# SENSE.net
KiCad netlist of a schematic drawn in Altium Designer
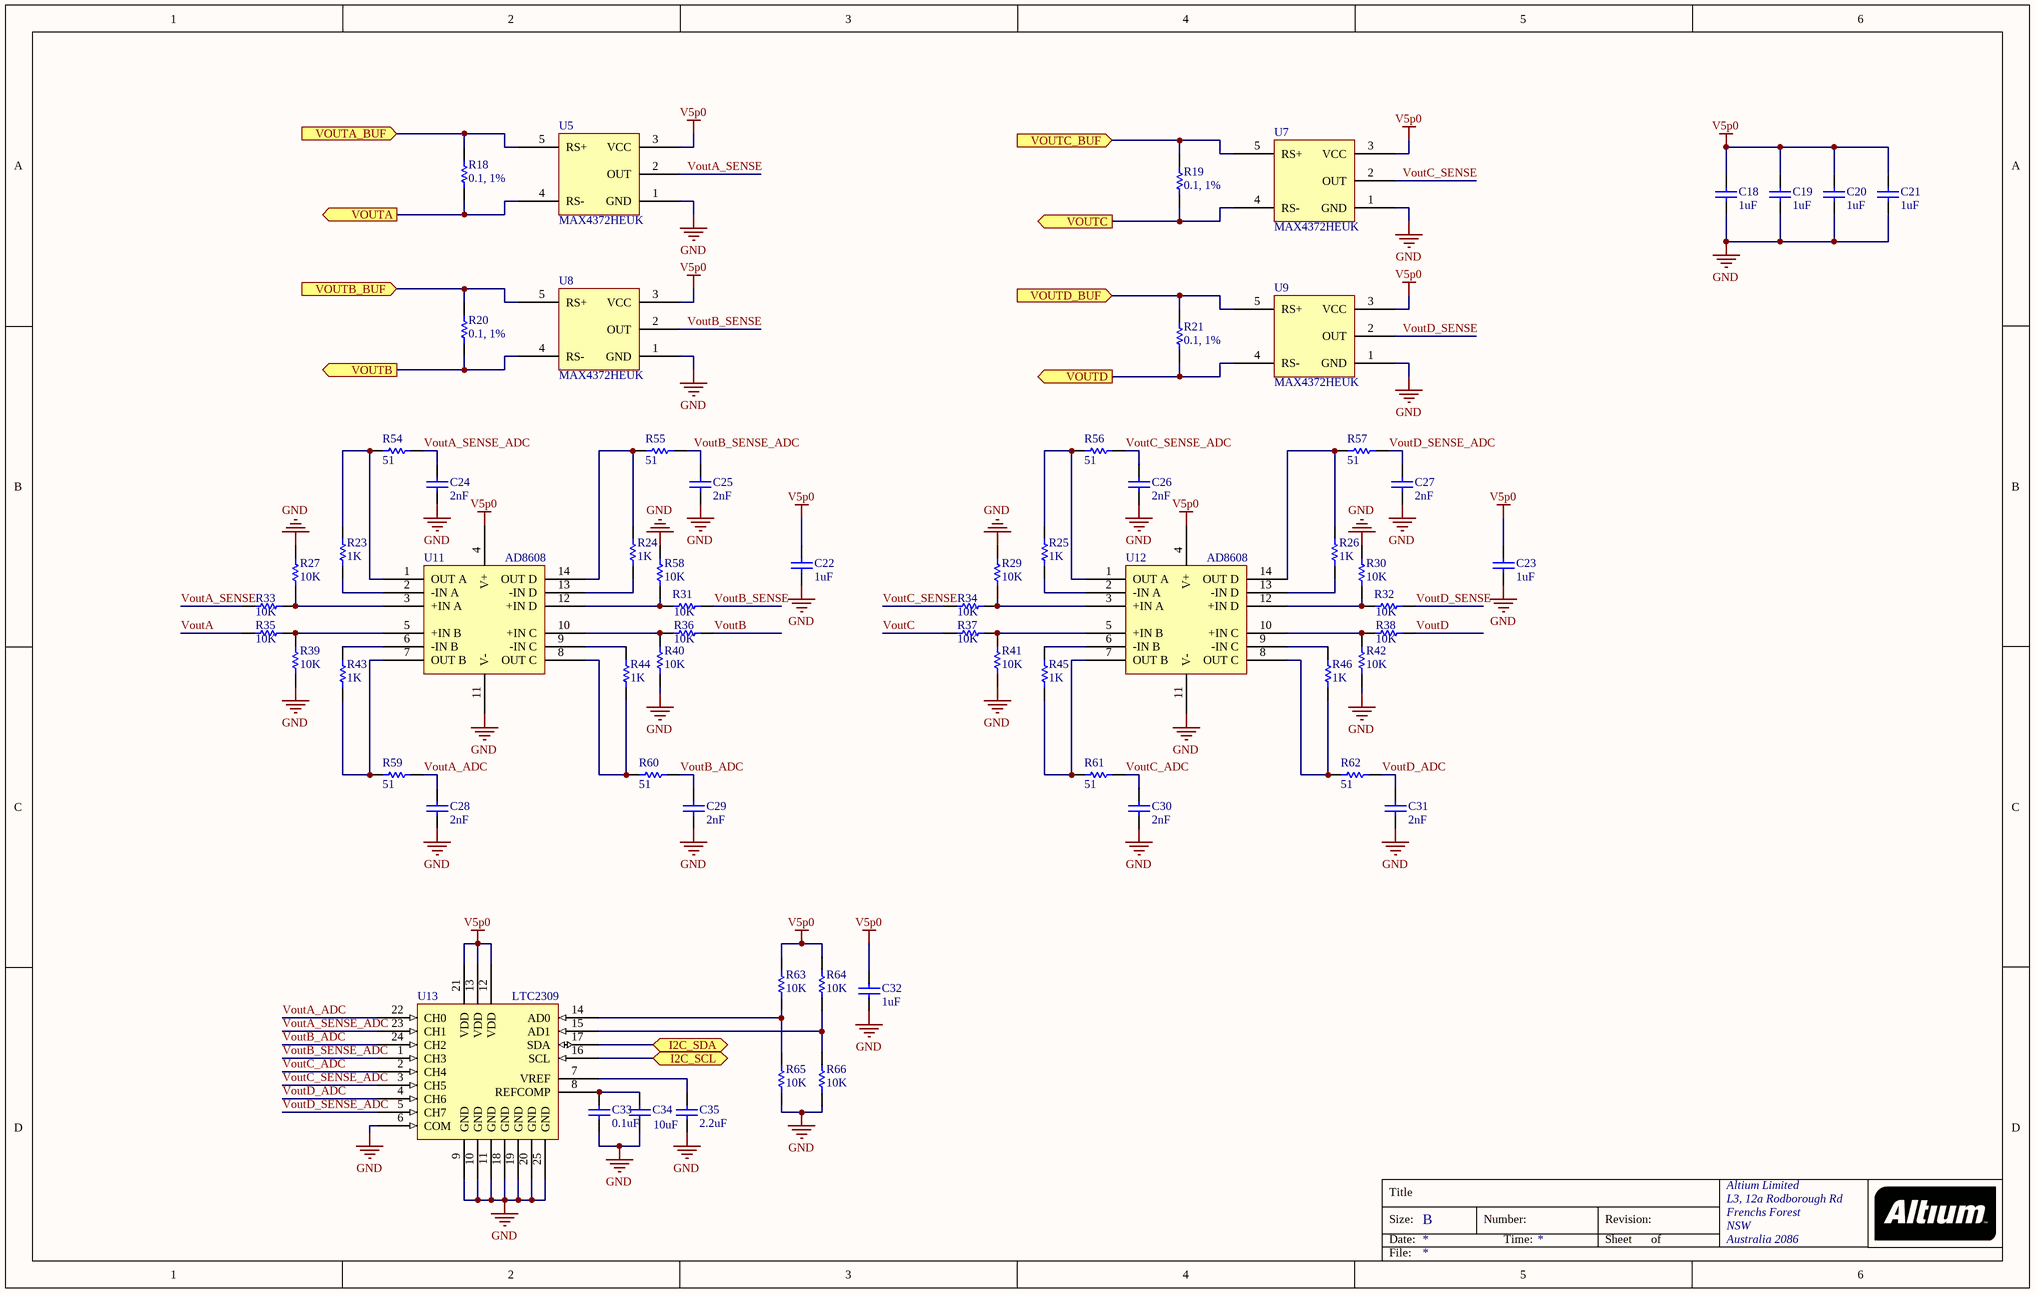
[diagram p0: SENSE.SchDoc]

(export (version "E")
  (design (tool "Eeschema 10.0.6"))
  (components
    (comp (ref "C18")
      (value "1uF")
      (footprint "CAPC01005(0402)22_N")
      (fields (field (name "Comment") "CAP, 0402, 1uF"))
      (libsource (lib "Components") (part "CAP, 0402, 1uF"))
    )
    (comp (ref "C19")
      (value "1uF")
      (footprint "CAPC01005(0402)22_N")
      (fields (field (name "Comment") "CAP, 0402, 1uF"))
      (libsource (lib "Components") (part "CAP, 0402, 1uF"))
    )
    (comp (ref "C20")
      (value "1uF")
      (footprint "CAPC01005(0402)22_N")
      (fields (field (name "Comment") "CAP, 0402, 1uF"))
      (libsource (lib "Components") (part "CAP, 0402, 1uF"))
    )
    (comp (ref "C21")
      (value "1uF")
      (footprint "CAPC01005(0402)22_N")
      (fields (field (name "Comment") "CAP, 0402, 1uF"))
      (libsource (lib "Components") (part "CAP, 0402, 1uF"))
    )
    (comp (ref "C22")
      (value "1uF")
      (footprint "CAPC01005(0402)22_N")
      (fields (field (name "Comment") "CAP, 0402, 1uF"))
      (libsource (lib "Components") (part "CAP, 0402, 1uF"))
    )
    (comp (ref "C23")
      (value "1uF")
      (footprint "CAPC01005(0402)22_N")
      (fields (field (name "Comment") "CAP, 0402, 1uF"))
      (libsource (lib "Components") (part "CAP, 0402, 1uF"))
    )
    (comp (ref "C24")
      (value "2nF")
      (footprint "CAPC01005(0402)22_N")
      (fields (field (name "Comment") "CAP, 0402, 2nF"))
      (libsource (lib "Components") (part "CAP, 0402, 2nF"))
    )
    (comp (ref "C25")
      (value "2nF")
      (footprint "CAPC01005(0402)22_N")
      (fields (field (name "Comment") "CAP, 0402, 2nF"))
      (libsource (lib "Components") (part "CAP, 0402, 2nF"))
    )
    (comp (ref "C26")
      (value "2nF")
      (footprint "CAPC01005(0402)22_N")
      (fields (field (name "Comment") "CAP, 0402, 2nF"))
      (libsource (lib "Components") (part "CAP, 0402, 2nF"))
    )
    (comp (ref "C27")
      (value "2nF")
      (footprint "CAPC01005(0402)22_N")
      (fields (field (name "Comment") "CAP, 0402, 2nF"))
      (libsource (lib "Components") (part "CAP, 0402, 2nF"))
    )
    (comp (ref "C28")
      (value "2nF")
      (footprint "CAPC01005(0402)22_N")
      (fields (field (name "Comment") "CAP, 0402, 2nF"))
      (libsource (lib "Components") (part "CAP, 0402, 2nF"))
    )
    (comp (ref "C29")
      (value "2nF")
      (footprint "CAPC01005(0402)22_N")
      (fields (field (name "Comment") "CAP, 0402, 2nF"))
      (libsource (lib "Components") (part "CAP, 0402, 2nF"))
    )
    (comp (ref "C30")
      (value "2nF")
      (footprint "CAPC01005(0402)22_N")
      (fields (field (name "Comment") "CAP, 0402, 2nF"))
      (libsource (lib "Components") (part "CAP, 0402, 2nF"))
    )
    (comp (ref "C31")
      (value "2nF")
      (footprint "CAPC01005(0402)22_N")
      (fields (field (name "Comment") "CAP, 0402, 2nF"))
      (libsource (lib "Components") (part "CAP, 0402, 2nF"))
    )
    (comp (ref "C32")
      (value "1uF")
      (footprint "CAPC01005(0402)22_N")
      (fields (field (name "Comment") "CAP, 0402, 1uF"))
      (libsource (lib "Components") (part "CAP, 0402, 1uF"))
    )
    (comp (ref "C33")
      (value "0.1uF")
      (footprint "CAPC01005(0402)22_N")
      (fields (field (name "Comment") "CAP, 0402, 0.1uF"))
      (libsource (lib "Components") (part "CAP, 0402, 0.1uF"))
    )
    (comp (ref "C34")
      (value "10uF")
      (footprint "CAPC0805(2012)130_N")
      (fields (field (name "Comment") "CAP, 0805, 10uF"))
      (libsource (lib "Components") (part "CAP, 0805, 10uF"))
    )
    (comp (ref "C35")
      (value "2.2uF")
      (footprint "CAPC01005(0402)22_N")
      (fields (field (name "Comment") "CAP, 0402, 2.2uF"))
      (libsource (lib "Components") (part "CAP, 0402, 2.2uF"))
    )
    (comp (ref "R18")
      (value "0.1, 1%")
      (footprint "RES, 0603")
      (fields
        (field (name "TOLERANCE") "±1%")
        (field (name "MANUFACTURER") "Panasonic Electronic Components")
        (field (name "MANUFACTURER PART NUMBER") "ERJ-3RSFR10V")
      )
      (libsource (lib "Components") (part "RES, 0603, 0.1, 1%"))
    )
    (comp (ref "R19")
      (value "0.1, 1%")
      (footprint "RES, 0603")
      (fields
        (field (name "TOLERANCE") "±1%")
        (field (name "MANUFACTURER") "Panasonic Electronic Components")
        (field (name "MANUFACTURER PART NUMBER") "ERJ-3RSFR10V")
      )
      (libsource (lib "Components") (part "RES, 0603, 0.1, 1%"))
    )
    (comp (ref "R20")
      (value "0.1, 1%")
      (footprint "RES, 0603")
      (fields
        (field (name "TOLERANCE") "±1%")
        (field (name "MANUFACTURER") "Panasonic Electronic Components")
        (field (name "MANUFACTURER PART NUMBER") "ERJ-3RSFR10V")
      )
      (libsource (lib "Components") (part "RES, 0603, 0.1, 1%"))
    )
    (comp (ref "R21")
      (value "0.1, 1%")
      (footprint "RES, 0603")
      (fields
        (field (name "TOLERANCE") "±1%")
        (field (name "MANUFACTURER") "Panasonic Electronic Components")
        (field (name "MANUFACTURER PART NUMBER") "ERJ-3RSFR10V")
      )
      (libsource (lib "Components") (part "RES, 0603, 0.1, 1%"))
    )
    (comp (ref "R23")
      (value "1K")
      (footprint "RES, 0603")
      (description "Resistor, 0603, 1/10W, 1K ohm")
      (fields
        (field (name "MANUFACTURER") "Panasonic Electronic Components")
        (field (name "MANUFACTURER PART NUMBER") "ERJ-3EKF1001V")
      )
      (libsource (lib "Resistors0603") (part "RES_0603_1K"))
    )
    (comp (ref "R24")
      (value "1K")
      (footprint "RES, 0603")
      (description "Resistor, 0603, 1/10W, 1K ohm")
      (fields
        (field (name "MANUFACTURER") "Panasonic Electronic Components")
        (field (name "MANUFACTURER PART NUMBER") "ERJ-3EKF1001V")
      )
      (libsource (lib "Resistors0603") (part "RES_0603_1K"))
    )
    (comp (ref "R25")
      (value "1K")
      (footprint "RES, 0603")
      (description "Resistor, 0603, 1/10W, 1K ohm")
      (fields
        (field (name "MANUFACTURER") "Panasonic Electronic Components")
        (field (name "MANUFACTURER PART NUMBER") "ERJ-3EKF1001V")
      )
      (libsource (lib "Resistors0603") (part "RES_0603_1K"))
    )
    (comp (ref "R26")
      (value "1K")
      (footprint "RES, 0603")
      (description "Resistor, 0603, 1/10W, 1K ohm")
      (fields
        (field (name "MANUFACTURER") "Panasonic Electronic Components")
        (field (name "MANUFACTURER PART NUMBER") "ERJ-3EKF1001V")
      )
      (libsource (lib "Resistors0603") (part "RES_0603_1K"))
    )
    (comp (ref "R27")
      (value "10K")
      (footprint "RES, 0603")
      (description "Resistor, 0603, 1/10W, 10K ohm")
      (fields
        (field (name "MANUFACTURER") "Panasonic Electronic Components")
        (field (name "MANUFACTURER PART NUMBER") "ERJ-3EKF1002V")
      )
      (libsource (lib "Resistors0603") (part "RES_0603_10K"))
    )
    (comp (ref "R29")
      (value "10K")
      (footprint "RES, 0603")
      (description "Resistor, 0603, 1/10W, 10K ohm")
      (fields
        (field (name "MANUFACTURER") "Panasonic Electronic Components")
        (field (name "MANUFACTURER PART NUMBER") "ERJ-3EKF1002V")
      )
      (libsource (lib "Resistors0603") (part "RES_0603_10K"))
    )
    (comp (ref "R30")
      (value "10K")
      (footprint "RES, 0603")
      (description "Resistor, 0603, 1/10W, 10K ohm")
      (fields
        (field (name "MANUFACTURER") "Panasonic Electronic Components")
        (field (name "MANUFACTURER PART NUMBER") "ERJ-3EKF1002V")
      )
      (libsource (lib "Resistors0603") (part "RES_0603_10K"))
    )
    (comp (ref "R31")
      (value "10K")
      (footprint "RES, 0603")
      (description "Resistor, 0603, 1/10W, 10K ohm")
      (fields
        (field (name "MANUFACTURER") "Panasonic Electronic Components")
        (field (name "MANUFACTURER PART NUMBER") "ERJ-3EKF1002V")
      )
      (libsource (lib "Resistors0603") (part "RES_0603_10K"))
    )
    (comp (ref "R32")
      (value "10K")
      (footprint "RES, 0603")
      (description "Resistor, 0603, 1/10W, 10K ohm")
      (fields
        (field (name "MANUFACTURER") "Panasonic Electronic Components")
        (field (name "MANUFACTURER PART NUMBER") "ERJ-3EKF1002V")
      )
      (libsource (lib "Resistors0603") (part "RES_0603_10K"))
    )
    (comp (ref "R33")
      (value "10K")
      (footprint "RES, 0603")
      (description "Resistor, 0603, 1/10W, 10K ohm")
      (fields
        (field (name "MANUFACTURER") "Panasonic Electronic Components")
        (field (name "MANUFACTURER PART NUMBER") "ERJ-3EKF1002V")
      )
      (libsource (lib "Resistors0603") (part "RES_0603_10K"))
    )
    (comp (ref "R34")
      (value "10K")
      (footprint "RES, 0603")
      (description "Resistor, 0603, 1/10W, 10K ohm")
      (fields
        (field (name "MANUFACTURER") "Panasonic Electronic Components")
        (field (name "MANUFACTURER PART NUMBER") "ERJ-3EKF1002V")
      )
      (libsource (lib "Resistors0603") (part "RES_0603_10K"))
    )
    (comp (ref "R35")
      (value "10K")
      (footprint "RES, 0603")
      (description "Resistor, 0603, 1/10W, 10K ohm")
      (fields
        (field (name "MANUFACTURER") "Panasonic Electronic Components")
        (field (name "MANUFACTURER PART NUMBER") "ERJ-3EKF1002V")
      )
      (libsource (lib "Resistors0603") (part "RES_0603_10K"))
    )
    (comp (ref "R36")
      (value "10K")
      (footprint "RES, 0603")
      (description "Resistor, 0603, 1/10W, 10K ohm")
      (fields
        (field (name "MANUFACTURER") "Panasonic Electronic Components")
        (field (name "MANUFACTURER PART NUMBER") "ERJ-3EKF1002V")
      )
      (libsource (lib "Resistors0603") (part "RES_0603_10K"))
    )
    (comp (ref "R37")
      (value "10K")
      (footprint "RES, 0603")
      (description "Resistor, 0603, 1/10W, 10K ohm")
      (fields
        (field (name "MANUFACTURER") "Panasonic Electronic Components")
        (field (name "MANUFACTURER PART NUMBER") "ERJ-3EKF1002V")
      )
      (libsource (lib "Resistors0603") (part "RES_0603_10K"))
    )
    (comp (ref "R38")
      (value "10K")
      (footprint "RES, 0603")
      (description "Resistor, 0603, 1/10W, 10K ohm")
      (fields
        (field (name "MANUFACTURER") "Panasonic Electronic Components")
        (field (name "MANUFACTURER PART NUMBER") "ERJ-3EKF1002V")
      )
      (libsource (lib "Resistors0603") (part "RES_0603_10K"))
    )
    (comp (ref "R39")
      (value "10K")
      (footprint "RES, 0603")
      (description "Resistor, 0603, 1/10W, 10K ohm")
      (fields
        (field (name "MANUFACTURER") "Panasonic Electronic Components")
        (field (name "MANUFACTURER PART NUMBER") "ERJ-3EKF1002V")
      )
      (libsource (lib "Resistors0603") (part "RES_0603_10K"))
    )
    (comp (ref "R40")
      (value "10K")
      (footprint "RES, 0603")
      (description "Resistor, 0603, 1/10W, 10K ohm")
      (fields
        (field (name "MANUFACTURER") "Panasonic Electronic Components")
        (field (name "MANUFACTURER PART NUMBER") "ERJ-3EKF1002V")
      )
      (libsource (lib "Resistors0603") (part "RES_0603_10K"))
    )
    (comp (ref "R41")
      (value "10K")
      (footprint "RES, 0603")
      (description "Resistor, 0603, 1/10W, 10K ohm")
      (fields
        (field (name "MANUFACTURER") "Panasonic Electronic Components")
        (field (name "MANUFACTURER PART NUMBER") "ERJ-3EKF1002V")
      )
      (libsource (lib "Resistors0603") (part "RES_0603_10K"))
    )
    (comp (ref "R42")
      (value "10K")
      (footprint "RES, 0603")
      (description "Resistor, 0603, 1/10W, 10K ohm")
      (fields
        (field (name "MANUFACTURER") "Panasonic Electronic Components")
        (field (name "MANUFACTURER PART NUMBER") "ERJ-3EKF1002V")
      )
      (libsource (lib "Resistors0603") (part "RES_0603_10K"))
    )
    (comp (ref "R43")
      (value "1K")
      (footprint "RES, 0603")
      (description "Resistor, 0603, 1/10W, 1K ohm")
      (fields
        (field (name "MANUFACTURER") "Panasonic Electronic Components")
        (field (name "MANUFACTURER PART NUMBER") "ERJ-3EKF1001V")
      )
      (libsource (lib "Resistors0603") (part "RES_0603_1K"))
    )
    (comp (ref "R44")
      (value "1K")
      (footprint "RES, 0603")
      (description "Resistor, 0603, 1/10W, 1K ohm")
      (fields
        (field (name "MANUFACTURER") "Panasonic Electronic Components")
        (field (name "MANUFACTURER PART NUMBER") "ERJ-3EKF1001V")
      )
      (libsource (lib "Resistors0603") (part "RES_0603_1K"))
    )
    (comp (ref "R45")
      (value "1K")
      (footprint "RES, 0603")
      (description "Resistor, 0603, 1/10W, 1K ohm")
      (fields
        (field (name "MANUFACTURER") "Panasonic Electronic Components")
        (field (name "MANUFACTURER PART NUMBER") "ERJ-3EKF1001V")
      )
      (libsource (lib "Resistors0603") (part "RES_0603_1K"))
    )
    (comp (ref "R46")
      (value "1K")
      (footprint "RES, 0603")
      (description "Resistor, 0603, 1/10W, 1K ohm")
      (fields
        (field (name "MANUFACTURER") "Panasonic Electronic Components")
        (field (name "MANUFACTURER PART NUMBER") "ERJ-3EKF1001V")
      )
      (libsource (lib "Resistors0603") (part "RES_0603_1K"))
    )
    (comp (ref "R54")
      (value "51")
      (footprint "RES, 0603")
      (description "Resistor, 0603, 1/10W, 51 ohm")
      (fields
        (field (name "MANUFACTURER") "Panasonic Electronic Components")
        (field (name "MANUFACTURER PART NUMBER") "ERJ-3EKF51R0V")
      )
      (libsource (lib "Resistors0603") (part "RES_0603_51"))
    )
    (comp (ref "R55")
      (value "51")
      (footprint "RES, 0603")
      (description "Resistor, 0603, 1/10W, 51 ohm")
      (fields
        (field (name "MANUFACTURER") "Panasonic Electronic Components")
        (field (name "MANUFACTURER PART NUMBER") "ERJ-3EKF51R0V")
      )
      (libsource (lib "Resistors0603") (part "RES_0603_51"))
    )
    (comp (ref "R56")
      (value "51")
      (footprint "RES, 0603")
      (description "Resistor, 0603, 1/10W, 51 ohm")
      (fields
        (field (name "MANUFACTURER") "Panasonic Electronic Components")
        (field (name "MANUFACTURER PART NUMBER") "ERJ-3EKF51R0V")
      )
      (libsource (lib "Resistors0603") (part "RES_0603_51"))
    )
    (comp (ref "R57")
      (value "51")
      (footprint "RES, 0603")
      (description "Resistor, 0603, 1/10W, 51 ohm")
      (fields
        (field (name "MANUFACTURER") "Panasonic Electronic Components")
        (field (name "MANUFACTURER PART NUMBER") "ERJ-3EKF51R0V")
      )
      (libsource (lib "Resistors0603") (part "RES_0603_51"))
    )
    (comp (ref "R58")
      (value "10K")
      (footprint "RES, 0603")
      (description "Resistor, 0603, 1/10W, 10K ohm")
      (fields
        (field (name "MANUFACTURER") "Panasonic Electronic Components")
        (field (name "MANUFACTURER PART NUMBER") "ERJ-3EKF1002V")
      )
      (libsource (lib "Resistors0603") (part "RES_0603_10K"))
    )
    (comp (ref "R59")
      (value "51")
      (footprint "RES, 0603")
      (description "Resistor, 0603, 1/10W, 51 ohm")
      (fields
        (field (name "MANUFACTURER") "Panasonic Electronic Components")
        (field (name "MANUFACTURER PART NUMBER") "ERJ-3EKF51R0V")
      )
      (libsource (lib "Resistors0603") (part "RES_0603_51"))
    )
    (comp (ref "R60")
      (value "51")
      (footprint "RES, 0603")
      (description "Resistor, 0603, 1/10W, 51 ohm")
      (fields
        (field (name "MANUFACTURER") "Panasonic Electronic Components")
        (field (name "MANUFACTURER PART NUMBER") "ERJ-3EKF51R0V")
      )
      (libsource (lib "Resistors0603") (part "RES_0603_51"))
    )
    (comp (ref "R61")
      (value "51")
      (footprint "RES, 0603")
      (description "Resistor, 0603, 1/10W, 51 ohm")
      (fields
        (field (name "MANUFACTURER") "Panasonic Electronic Components")
        (field (name "MANUFACTURER PART NUMBER") "ERJ-3EKF51R0V")
      )
      (libsource (lib "Resistors0603") (part "RES_0603_51"))
    )
    (comp (ref "R62")
      (value "51")
      (footprint "RES, 0603")
      (description "Resistor, 0603, 1/10W, 51 ohm")
      (fields
        (field (name "MANUFACTURER") "Panasonic Electronic Components")
        (field (name "MANUFACTURER PART NUMBER") "ERJ-3EKF51R0V")
      )
      (libsource (lib "Resistors0603") (part "RES_0603_51"))
    )
    (comp (ref "R63")
      (value "10K")
      (footprint "RES, 0603")
      (description "Resistor, 0603, 1/10W, 10K ohm")
      (fields
        (field (name "MANUFACTURER") "Panasonic Electronic Components")
        (field (name "MANUFACTURER PART NUMBER") "ERJ-3EKF1002V")
      )
      (libsource (lib "Resistors0603") (part "RES_0603_10K"))
    )
    (comp (ref "R64")
      (value "10K")
      (footprint "RES, 0603")
      (description "Resistor, 0603, 1/10W, 10K ohm")
      (fields
        (field (name "MANUFACTURER") "Panasonic Electronic Components")
        (field (name "MANUFACTURER PART NUMBER") "ERJ-3EKF1002V")
      )
      (libsource (lib "Resistors0603") (part "RES_0603_10K"))
    )
    (comp (ref "R65")
      (value "10K")
      (footprint "RES, 0603")
      (description "Resistor, 0603, 1/10W, 10K ohm")
      (fields
        (field (name "MANUFACTURER") "Panasonic Electronic Components")
        (field (name "MANUFACTURER PART NUMBER") "ERJ-3EKF1002V")
      )
      (libsource (lib "Resistors0603") (part "RES_0603_10K"))
    )
    (comp (ref "R66")
      (value "10K")
      (footprint "RES, 0603")
      (description "Resistor, 0603, 1/10W, 10K ohm")
      (fields
        (field (name "MANUFACTURER") "Panasonic Electronic Components")
        (field (name "MANUFACTURER PART NUMBER") "ERJ-3EKF1002V")
      )
      (libsource (lib "Resistors0603") (part "RES_0603_10K"))
    )
    (comp (ref "U5")
      (value "MAX4372HEUK")
      (footprint "SOT23-5, MAX4372H")
      (fields (field (name "MANUFACTURER") "Maxim"))
      (libsource (lib "Components") (part "MAX4372H, Current-Sense, SOT23"))
    )
    (comp (ref "U7")
      (value "MAX4372HEUK")
      (footprint "SOT23-5, MAX4372H")
      (fields (field (name "MANUFACTURER") "Maxim"))
      (libsource (lib "Components") (part "MAX4372H, Current-Sense, SOT23"))
    )
    (comp (ref "U8")
      (value "MAX4372HEUK")
      (footprint "SOT23-5, MAX4372H")
      (fields (field (name "MANUFACTURER") "Maxim"))
      (libsource (lib "Components") (part "MAX4372H, Current-Sense, SOT23"))
    )
    (comp (ref "U9")
      (value "MAX4372HEUK")
      (footprint "SOT23-5, MAX4372H")
      (fields (field (name "MANUFACTURER") "Maxim"))
      (libsource (lib "Components") (part "MAX4372H, Current-Sense, SOT23"))
    )
    (comp (ref "U11")
      (value "AD8608")
      (footprint "TSOP65P640X120-14N")
      (description "IC OPAMP GP 10MHZ RRO 14SOIC")
      (fields
        (field (name "MANUFACTURER") "Analog Devices Inc")
        (field (name "MANUFACTURER PART NUMBER") "AD8608ARZ-REEL")
      )
      (libsource (lib "Components") (part "AD8608; Quad Op-Amp"))
    )
    (comp (ref "U12")
      (value "AD8608")
      (footprint "TSOP65P640X120-14N")
      (description "IC OPAMP GP 10MHZ RRO 14SOIC")
      (fields
        (field (name "MANUFACTURER") "Analog Devices Inc")
        (field (name "MANUFACTURER PART NUMBER") "AD8608ARZ-REEL")
      )
      (libsource (lib "Components") (part "AD8608; Quad Op-Amp"))
    )
    (comp (ref "U13")
      (value "LTC2309")
      (footprint "QFN50P400X400X80-24N")
      (description "8-Channel, 12-Bit SAR ADC with I2C Interface")
      (fields
        (field (name "MANUFACTURER") "Linear Technology")
        (field (name "MANUFACTURER PART NUMBER") "LTC2309CUF#PBF")
      )
      (libsource (lib "Components") (part "LTC2309"))
    )
  )
  (nets
    (net (code "1") (name "/I2C_SCL") (class "Default")
      (node (ref "U13") (pin "16") (pinfunction "SCL_16") (pintype "input"))
    )
    (net (code "2") (name "/I2C_SDA") (class "Default")
      (node (ref "U13") (pin "17") (pinfunction "SDA_17") (pintype "bidirectional"))
    )
    (net (code "3") (name "/VOUTA") (class "Default")
      (node (ref "R18") (pin "1") (pinfunction "1_1") (pintype "passive"))
      (node (ref "U5") (pin "4") (pinfunction "RS-_4") (pintype "passive"))
    )
    (net (code "4") (name "/VOUTA_BUF") (class "Default")
      (node (ref "R18") (pin "2") (pinfunction "2_2") (pintype "passive"))
      (node (ref "U5") (pin "5") (pinfunction "RS+_5") (pintype "passive"))
    )
    (net (code "5") (name "/VOUTB") (class "Default")
      (node (ref "R20") (pin "1") (pinfunction "1_1") (pintype "passive"))
      (node (ref "U8") (pin "4") (pinfunction "RS-_4") (pintype "passive"))
    )
    (net (code "6") (name "/VOUTB_BUF") (class "Default")
      (node (ref "R20") (pin "2") (pinfunction "2_2") (pintype "passive"))
      (node (ref "U8") (pin "5") (pinfunction "RS+_5") (pintype "passive"))
    )
    (net (code "7") (name "/VOUTC") (class "Default")
      (node (ref "R19") (pin "1") (pinfunction "1_1") (pintype "passive"))
      (node (ref "U7") (pin "4") (pinfunction "RS-_4") (pintype "passive"))
    )
    (net (code "8") (name "/VOUTC_BUF") (class "Default")
      (node (ref "R19") (pin "2") (pinfunction "2_2") (pintype "passive"))
      (node (ref "U7") (pin "5") (pinfunction "RS+_5") (pintype "passive"))
    )
    (net (code "9") (name "/VOUTD") (class "Default")
      (node (ref "R21") (pin "1") (pinfunction "1_1") (pintype "passive"))
      (node (ref "U9") (pin "4") (pinfunction "RS-_4") (pintype "passive"))
    )
    (net (code "10") (name "/VOUTD_BUF") (class "Default")
      (node (ref "R21") (pin "2") (pinfunction "2_2") (pintype "passive"))
      (node (ref "U9") (pin "5") (pinfunction "RS+_5") (pintype "passive"))
    )
    (net (code "11") (name "/VoutA") (class "Default")
      (node (ref "R35") (pin "1") (pinfunction "1_1") (pintype "passive"))
    )
    (net (code "12") (name "/VoutA_ADC") (class "Default")
      (node (ref "C28") (pin "1") (pinfunction "1_1") (pintype "passive"))
      (node (ref "R59") (pin "2") (pinfunction "2_2") (pintype "passive"))
      (node (ref "U13") (pin "22") (pinfunction "CH0_22") (pintype "input"))
    )
    (net (code "13") (name "/VoutA_SENSE") (class "Default")
      (node (ref "R33") (pin "1") (pinfunction "1_1") (pintype "passive"))
      (node (ref "U5") (pin "2") (pinfunction "OUT_2") (pintype "passive"))
    )
    (net (code "14") (name "/VoutA_SENSE_ADC") (class "Default")
      (node (ref "C24") (pin "1") (pinfunction "1_1") (pintype "passive"))
      (node (ref "R54") (pin "2") (pinfunction "2_2") (pintype "passive"))
      (node (ref "U13") (pin "23") (pinfunction "CH1_23") (pintype "input"))
    )
    (net (code "15") (name "/VoutB") (class "Default")
      (node (ref "R36") (pin "1") (pinfunction "1_1") (pintype "passive"))
    )
    (net (code "16") (name "/VoutB_ADC") (class "Default")
      (node (ref "C29") (pin "1") (pinfunction "1_1") (pintype "passive"))
      (node (ref "R60") (pin "2") (pinfunction "2_2") (pintype "passive"))
      (node (ref "U13") (pin "24") (pinfunction "CH2_24") (pintype "input"))
    )
    (net (code "17") (name "/VoutB_SENSE") (class "Default")
      (node (ref "R31") (pin "1") (pinfunction "1_1") (pintype "passive"))
      (node (ref "U8") (pin "2") (pinfunction "OUT_2") (pintype "passive"))
    )
    (net (code "18") (name "/VoutB_SENSE_ADC") (class "Default")
      (node (ref "C25") (pin "1") (pinfunction "1_1") (pintype "passive"))
      (node (ref "R55") (pin "2") (pinfunction "2_2") (pintype "passive"))
      (node (ref "U13") (pin "1") (pinfunction "CH3_1") (pintype "input"))
    )
    (net (code "19") (name "/VoutC") (class "Default")
      (node (ref "R37") (pin "1") (pinfunction "1_1") (pintype "passive"))
    )
    (net (code "20") (name "/VoutC_ADC") (class "Default")
      (node (ref "C30") (pin "1") (pinfunction "1_1") (pintype "passive"))
      (node (ref "R61") (pin "2") (pinfunction "2_2") (pintype "passive"))
      (node (ref "U13") (pin "2") (pinfunction "CH4_2") (pintype "input"))
    )
    (net (code "21") (name "/VoutC_SENSE") (class "Default")
      (node (ref "R34") (pin "1") (pinfunction "1_1") (pintype "passive"))
      (node (ref "U7") (pin "2") (pinfunction "OUT_2") (pintype "passive"))
    )
    (net (code "22") (name "/VoutC_SENSE_ADC") (class "Default")
      (node (ref "C26") (pin "1") (pinfunction "1_1") (pintype "passive"))
      (node (ref "R56") (pin "2") (pinfunction "2_2") (pintype "passive"))
      (node (ref "U13") (pin "3") (pinfunction "CH5_3") (pintype "input"))
    )
    (net (code "23") (name "/VoutD") (class "Default")
      (node (ref "R38") (pin "1") (pinfunction "1_1") (pintype "passive"))
    )
    (net (code "24") (name "/VoutD_ADC") (class "Default")
      (node (ref "C31") (pin "1") (pinfunction "1_1") (pintype "passive"))
      (node (ref "R62") (pin "2") (pinfunction "2_2") (pintype "passive"))
      (node (ref "U13") (pin "4") (pinfunction "CH6_4") (pintype "input"))
    )
    (net (code "25") (name "/VoutD_SENSE") (class "Default")
      (node (ref "R32") (pin "1") (pinfunction "1_1") (pintype "passive"))
      (node (ref "U9") (pin "2") (pinfunction "OUT_2") (pintype "passive"))
    )
    (net (code "26") (name "/VoutD_SENSE_ADC") (class "Default")
      (node (ref "C27") (pin "1") (pinfunction "1_1") (pintype "passive"))
      (node (ref "R57") (pin "2") (pinfunction "2_2") (pintype "passive"))
      (node (ref "U13") (pin "5") (pinfunction "CH7_5") (pintype "input"))
    )
    (net (code "27") (name "GND") (class "Default")
      (node (ref "C18") (pin "1") (pinfunction "1_1") (pintype "passive"))
      (node (ref "C19") (pin "1") (pinfunction "1_1") (pintype "passive"))
      (node (ref "C20") (pin "1") (pinfunction "1_1") (pintype "passive"))
      (node (ref "C21") (pin "1") (pinfunction "1_1") (pintype "passive"))
      (node (ref "C22") (pin "1") (pinfunction "1_1") (pintype "passive"))
      (node (ref "C23") (pin "1") (pinfunction "1_1") (pintype "passive"))
      (node (ref "C24") (pin "2") (pinfunction "2_2") (pintype "passive"))
      (node (ref "C25") (pin "2") (pinfunction "2_2") (pintype "passive"))
      (node (ref "C26") (pin "2") (pinfunction "2_2") (pintype "passive"))
      (node (ref "C27") (pin "2") (pinfunction "2_2") (pintype "passive"))
      (node (ref "C28") (pin "2") (pinfunction "2_2") (pintype "passive"))
      (node (ref "C29") (pin "2") (pinfunction "2_2") (pintype "passive"))
      (node (ref "C30") (pin "2") (pinfunction "2_2") (pintype "passive"))
      (node (ref "C31") (pin "2") (pinfunction "2_2") (pintype "passive"))
      (node (ref "C32") (pin "1") (pinfunction "1_1") (pintype "passive"))
      (node (ref "C33") (pin "1") (pinfunction "1_1") (pintype "passive"))
      (node (ref "C34") (pin "1") (pinfunction "1_1") (pintype "passive"))
      (node (ref "C35") (pin "1") (pinfunction "1_1") (pintype "passive"))
      (node (ref "R27") (pin "2") (pinfunction "2_2") (pintype "passive"))
      (node (ref "R29") (pin "2") (pinfunction "2_2") (pintype "passive"))
      (node (ref "R30") (pin "1") (pinfunction "1_1") (pintype "passive"))
      (node (ref "R39") (pin "1") (pinfunction "1_1") (pintype "passive"))
      (node (ref "R40") (pin "2") (pinfunction "2_2") (pintype "passive"))
      (node (ref "R41") (pin "1") (pinfunction "1_1") (pintype "passive"))
      (node (ref "R42") (pin "2") (pinfunction "2_2") (pintype "passive"))
      (node (ref "R58") (pin "1") (pinfunction "1_1") (pintype "passive"))
      (node (ref "R65") (pin "2") (pinfunction "2_2") (pintype "passive"))
      (node (ref "R66") (pin "2") (pinfunction "2_2") (pintype "passive"))
      (node (ref "U11") (pin "11") (pinfunction "V-_11") (pintype "passive"))
      (node (ref "U12") (pin "11") (pinfunction "V-_11") (pintype "passive"))
      (node (ref "U13") (pin "10") (pinfunction "GND_10") (pintype "power_in"))
      (node (ref "U13") (pin "11") (pinfunction "GND_11") (pintype "power_in"))
      (node (ref "U13") (pin "18") (pinfunction "GND_18") (pintype "power_in"))
      (node (ref "U13") (pin "19") (pinfunction "GND_19") (pintype "power_in"))
      (node (ref "U13") (pin "20") (pinfunction "GND_20") (pintype "power_in"))
      (node (ref "U13") (pin "25") (pinfunction "GND_25") (pintype "power_in"))
      (node (ref "U13") (pin "6") (pinfunction "COM_6") (pintype "input"))
      (node (ref "U13") (pin "9") (pinfunction "GND_9") (pintype "power_in"))
      (node (ref "U5") (pin "1") (pinfunction "GND_1") (pintype "passive"))
      (node (ref "U7") (pin "1") (pinfunction "GND_1") (pintype "passive"))
      (node (ref "U8") (pin "1") (pinfunction "GND_1") (pintype "passive"))
      (node (ref "U9") (pin "1") (pinfunction "GND_1") (pintype "passive"))
    )
    (net (code "28") (name "Net-(U11-+IN_A)") (class "Default")
      (node (ref "R27") (pin "1") (pinfunction "1_1") (pintype "passive"))
      (node (ref "R33") (pin "2") (pinfunction "2_2") (pintype "passive"))
      (node (ref "U11") (pin "3") (pinfunction "+IN_A_3") (pintype "passive"))
    )
    (net (code "29") (name "Net-(U11-+IN_B)") (class "Default")
      (node (ref "R35") (pin "2") (pinfunction "2_2") (pintype "passive"))
      (node (ref "R39") (pin "2") (pinfunction "2_2") (pintype "passive"))
      (node (ref "U11") (pin "5") (pinfunction "+IN_B_5") (pintype "passive"))
    )
    (net (code "30") (name "Net-(U11-+IN_C)") (class "Default")
      (node (ref "R36") (pin "2") (pinfunction "2_2") (pintype "passive"))
      (node (ref "R40") (pin "1") (pinfunction "1_1") (pintype "passive"))
      (node (ref "U11") (pin "10") (pinfunction "+IN_C_10") (pintype "passive"))
    )
    (net (code "31") (name "Net-(U11-+IN_D)") (class "Default")
      (node (ref "R31") (pin "2") (pinfunction "2_2") (pintype "passive"))
      (node (ref "R58") (pin "2") (pinfunction "2_2") (pintype "passive"))
      (node (ref "U11") (pin "12") (pinfunction "+IN_D_12") (pintype "passive"))
    )
    (net (code "32") (name "Net-(U11--IN_A)") (class "Default")
      (node (ref "R23") (pin "1") (pinfunction "1_1") (pintype "passive"))
      (node (ref "U11") (pin "2") (pinfunction "-IN_A_2") (pintype "passive"))
    )
    (net (code "33") (name "Net-(U11--IN_B)") (class "Default")
      (node (ref "R43") (pin "2") (pinfunction "2_2") (pintype "passive"))
      (node (ref "U11") (pin "6") (pinfunction "-IN_B_6") (pintype "passive"))
    )
    (net (code "34") (name "Net-(U11--IN_C)") (class "Default")
      (node (ref "R44") (pin "2") (pinfunction "2_2") (pintype "passive"))
      (node (ref "U11") (pin "9") (pinfunction "-IN_C_9") (pintype "passive"))
    )
    (net (code "35") (name "Net-(U11--IN_D)") (class "Default")
      (node (ref "R24") (pin "1") (pinfunction "1_1") (pintype "passive"))
      (node (ref "U11") (pin "13") (pinfunction "-IN_D_13") (pintype "passive"))
    )
    (net (code "36") (name "Net-(U11-OUT_A)") (class "Default")
      (node (ref "R23") (pin "2") (pinfunction "2_2") (pintype "passive"))
      (node (ref "R54") (pin "1") (pinfunction "1_1") (pintype "passive"))
      (node (ref "U11") (pin "1") (pinfunction "OUT_A_1") (pintype "passive"))
    )
    (net (code "37") (name "Net-(U11-OUT_B)") (class "Default")
      (node (ref "R43") (pin "1") (pinfunction "1_1") (pintype "passive"))
      (node (ref "R59") (pin "1") (pinfunction "1_1") (pintype "passive"))
      (node (ref "U11") (pin "7") (pinfunction "OUT_B_7") (pintype "passive"))
    )
    (net (code "38") (name "Net-(U11-OUT_C)") (class "Default")
      (node (ref "R44") (pin "1") (pinfunction "1_1") (pintype "passive"))
      (node (ref "R60") (pin "1") (pinfunction "1_1") (pintype "passive"))
      (node (ref "U11") (pin "8") (pinfunction "OUT_C_8") (pintype "passive"))
    )
    (net (code "39") (name "Net-(U11-OUT_D)") (class "Default")
      (node (ref "R24") (pin "2") (pinfunction "2_2") (pintype "passive"))
      (node (ref "R55") (pin "1") (pinfunction "1_1") (pintype "passive"))
      (node (ref "U11") (pin "14") (pinfunction "OUT_D_14") (pintype "passive"))
    )
    (net (code "40") (name "Net-(U12-+IN_A)") (class "Default")
      (node (ref "R29") (pin "1") (pinfunction "1_1") (pintype "passive"))
      (node (ref "R34") (pin "2") (pinfunction "2_2") (pintype "passive"))
      (node (ref "U12") (pin "3") (pinfunction "+IN_A_3") (pintype "passive"))
    )
    (net (code "41") (name "Net-(U12-+IN_B)") (class "Default")
      (node (ref "R37") (pin "2") (pinfunction "2_2") (pintype "passive"))
      (node (ref "R41") (pin "2") (pinfunction "2_2") (pintype "passive"))
      (node (ref "U12") (pin "5") (pinfunction "+IN_B_5") (pintype "passive"))
    )
    (net (code "42") (name "Net-(U12-+IN_C)") (class "Default")
      (node (ref "R38") (pin "2") (pinfunction "2_2") (pintype "passive"))
      (node (ref "R42") (pin "1") (pinfunction "1_1") (pintype "passive"))
      (node (ref "U12") (pin "10") (pinfunction "+IN_C_10") (pintype "passive"))
    )
    (net (code "43") (name "Net-(U12-+IN_D)") (class "Default")
      (node (ref "R30") (pin "2") (pinfunction "2_2") (pintype "passive"))
      (node (ref "R32") (pin "2") (pinfunction "2_2") (pintype "passive"))
      (node (ref "U12") (pin "12") (pinfunction "+IN_D_12") (pintype "passive"))
    )
    (net (code "44") (name "Net-(U12--IN_A)") (class "Default")
      (node (ref "R25") (pin "1") (pinfunction "1_1") (pintype "passive"))
      (node (ref "U12") (pin "2") (pinfunction "-IN_A_2") (pintype "passive"))
    )
    (net (code "45") (name "Net-(U12--IN_B)") (class "Default")
      (node (ref "R45") (pin "2") (pinfunction "2_2") (pintype "passive"))
      (node (ref "U12") (pin "6") (pinfunction "-IN_B_6") (pintype "passive"))
    )
    (net (code "46") (name "Net-(U12--IN_C)") (class "Default")
      (node (ref "R46") (pin "2") (pinfunction "2_2") (pintype "passive"))
      (node (ref "U12") (pin "9") (pinfunction "-IN_C_9") (pintype "passive"))
    )
    (net (code "47") (name "Net-(U12--IN_D)") (class "Default")
      (node (ref "R26") (pin "1") (pinfunction "1_1") (pintype "passive"))
      (node (ref "U12") (pin "13") (pinfunction "-IN_D_13") (pintype "passive"))
    )
    (net (code "48") (name "Net-(U12-OUT_A)") (class "Default")
      (node (ref "R25") (pin "2") (pinfunction "2_2") (pintype "passive"))
      (node (ref "R56") (pin "1") (pinfunction "1_1") (pintype "passive"))
      (node (ref "U12") (pin "1") (pinfunction "OUT_A_1") (pintype "passive"))
    )
    (net (code "49") (name "Net-(U12-OUT_B)") (class "Default")
      (node (ref "R45") (pin "1") (pinfunction "1_1") (pintype "passive"))
      (node (ref "R61") (pin "1") (pinfunction "1_1") (pintype "passive"))
      (node (ref "U12") (pin "7") (pinfunction "OUT_B_7") (pintype "passive"))
    )
    (net (code "50") (name "Net-(U12-OUT_C)") (class "Default")
      (node (ref "R46") (pin "1") (pinfunction "1_1") (pintype "passive"))
      (node (ref "R62") (pin "1") (pinfunction "1_1") (pintype "passive"))
      (node (ref "U12") (pin "8") (pinfunction "OUT_C_8") (pintype "passive"))
    )
    (net (code "51") (name "Net-(U12-OUT_D)") (class "Default")
      (node (ref "R26") (pin "2") (pinfunction "2_2") (pintype "passive"))
      (node (ref "R57") (pin "1") (pinfunction "1_1") (pintype "passive"))
      (node (ref "U12") (pin "14") (pinfunction "OUT_D_14") (pintype "passive"))
    )
    (net (code "52") (name "Net-(U13-AD0)") (class "Default")
      (node (ref "R63") (pin "2") (pinfunction "2_2") (pintype "passive"))
      (node (ref "R65") (pin "1") (pinfunction "1_1") (pintype "passive"))
      (node (ref "U13") (pin "14") (pinfunction "AD0_14") (pintype "input"))
    )
    (net (code "53") (name "Net-(U13-AD1)") (class "Default")
      (node (ref "R64") (pin "2") (pinfunction "2_2") (pintype "passive"))
      (node (ref "R66") (pin "1") (pinfunction "1_1") (pintype "passive"))
      (node (ref "U13") (pin "15") (pinfunction "AD1_15") (pintype "input"))
    )
    (net (code "54") (name "Net-(U13-REFCOMP)") (class "Default")
      (node (ref "C33") (pin "2") (pinfunction "2_2") (pintype "passive"))
      (node (ref "C34") (pin "2") (pinfunction "2_2") (pintype "passive"))
      (node (ref "U13") (pin "8") (pinfunction "REFCOMP_8") (pintype "passive"))
    )
    (net (code "55") (name "Net-(U13-VREF)") (class "Default")
      (node (ref "C35") (pin "2") (pinfunction "2_2") (pintype "passive"))
      (node (ref "U13") (pin "7") (pinfunction "VREF_7") (pintype "passive"))
    )
    (net (code "56") (name "V5p0") (class "Default")
      (node (ref "C18") (pin "2") (pinfunction "2_2") (pintype "passive"))
      (node (ref "C19") (pin "2") (pinfunction "2_2") (pintype "passive"))
      (node (ref "C20") (pin "2") (pinfunction "2_2") (pintype "passive"))
      (node (ref "C21") (pin "2") (pinfunction "2_2") (pintype "passive"))
      (node (ref "C22") (pin "2") (pinfunction "2_2") (pintype "passive"))
      (node (ref "C23") (pin "2") (pinfunction "2_2") (pintype "passive"))
      (node (ref "C32") (pin "2") (pinfunction "2_2") (pintype "passive"))
      (node (ref "R63") (pin "1") (pinfunction "1_1") (pintype "passive"))
      (node (ref "R64") (pin "1") (pinfunction "1_1") (pintype "passive"))
      (node (ref "U11") (pin "4") (pinfunction "V+_4") (pintype "passive"))
      (node (ref "U12") (pin "4") (pinfunction "V+_4") (pintype "passive"))
      (node (ref "U13") (pin "12") (pinfunction "VDD_12") (pintype "power_in"))
      (node (ref "U13") (pin "13") (pinfunction "VDD_13") (pintype "power_in"))
      (node (ref "U13") (pin "21") (pinfunction "VDD_21") (pintype "power_in"))
      (node (ref "U5") (pin "3") (pinfunction "VCC_3") (pintype "passive"))
      (node (ref "U7") (pin "3") (pinfunction "VCC_3") (pintype "passive"))
      (node (ref "U8") (pin "3") (pinfunction "VCC_3") (pintype "passive"))
      (node (ref "U9") (pin "3") (pinfunction "VCC_3") (pintype "passive"))
    )
  )
)
